# efr32_lcd_hmi.net
KiCad netlist of a schematic drawn in Altium Designer
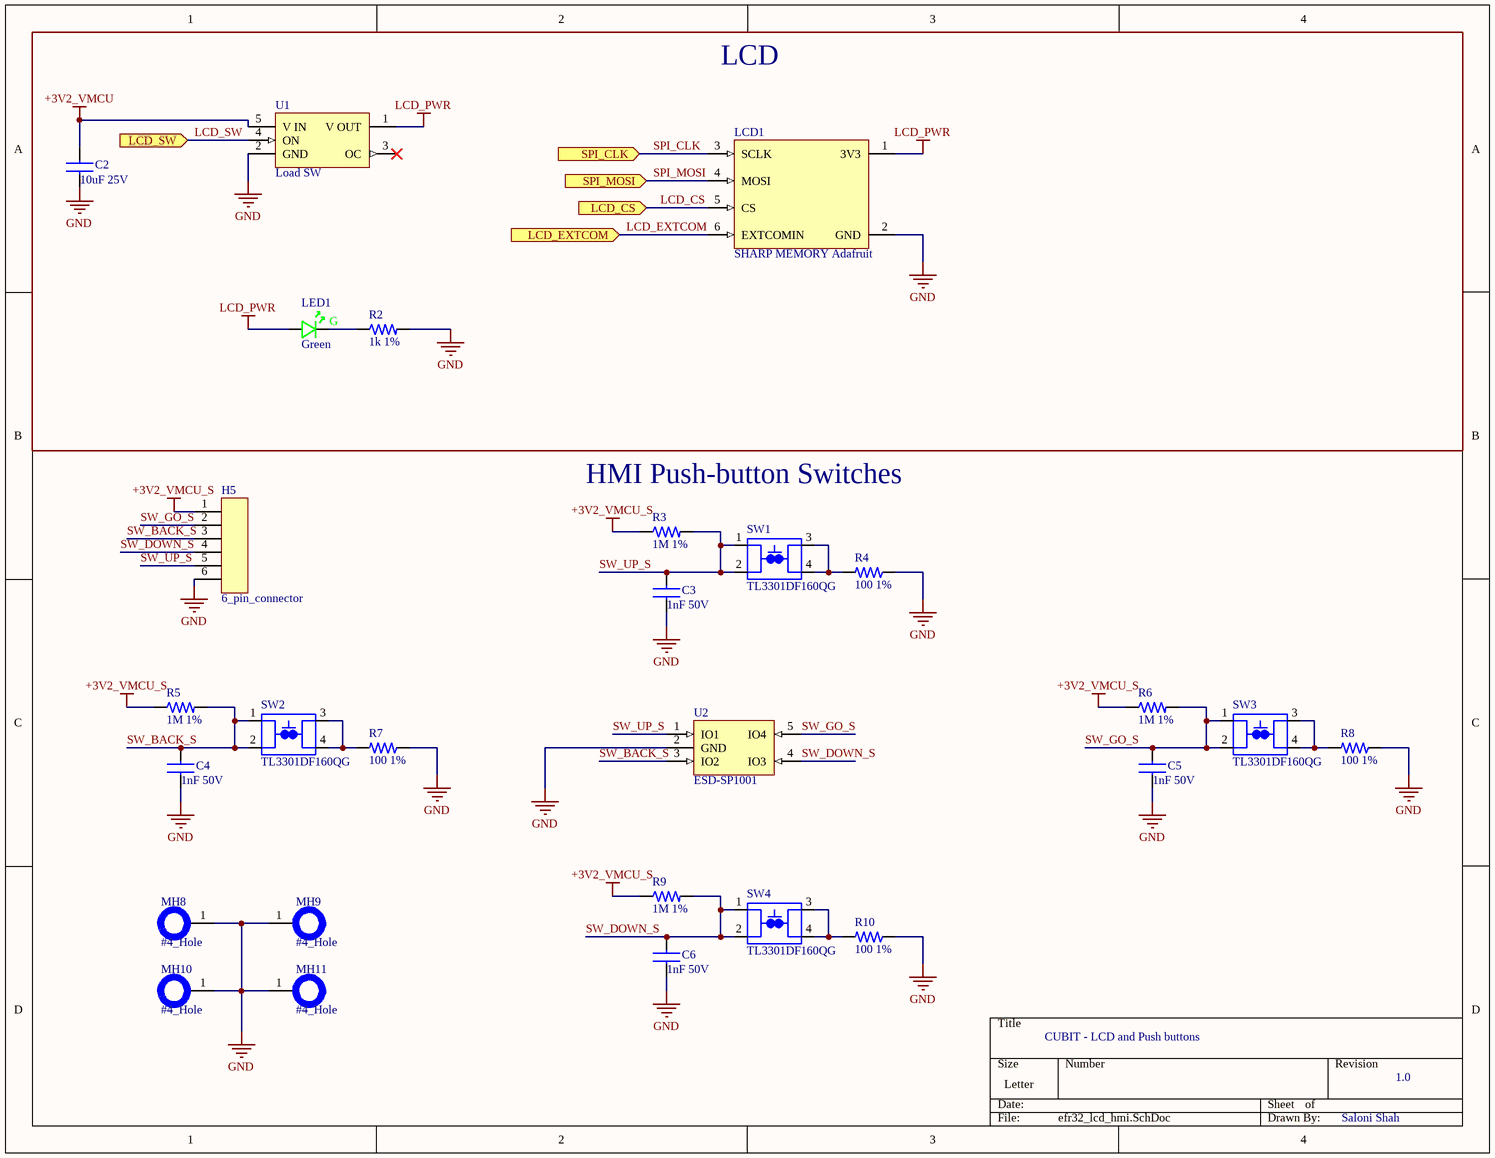
[diagram p0: efr32_lcd_hmi.SchDoc]

(export (version "E")
  (design (tool "Eeschema 10.0.6"))
  (components
    (comp (ref "C2")
      (value "10uF 25V")
      (footprint "LPEDT_proj_lib:CAP_0805_02X125")
      (description "Cap 0805 25 V 10 uF ±20% Tolerance X5R Monolithic Ceramic Chip Capacitor")
      (fields
        (field (name "MANUFACTURER") "Murata")
        (field (name "MANUFACTURER PART NUMBER") "GRM21BR61E106KA73K")
      )
      (libsource (lib "LPEDT_proj_lib") (part "GRM21BR61E106KA73K"))
    )
    (comp (ref "C3")
      (value "1nF 50V")
      (footprint "LPEDT_proj_lib:CAP_0805_02X125")
      (description "1nF ±10% 50V X7R 0805")
      (fields
        (field (name "MANUFACTURER") "Samsung")
        (field (name "MANUFACTURER PART NUMBER") "CL21B102KBANFNC")
      )
      (libsource (lib "LPEDT_proj_lib") (part "CL21B102KBANFNC"))
    )
    (comp (ref "C4")
      (value "1nF 50V")
      (footprint "LPEDT_proj_lib:CAP_0805_02X125")
      (description "1nF ±10% 50V X7R 0805")
      (fields
        (field (name "MANUFACTURER") "Samsung")
        (field (name "MANUFACTURER PART NUMBER") "CL21B102KBANFNC")
      )
      (libsource (lib "LPEDT_proj_lib") (part "CL21B102KBANFNC"))
    )
    (comp (ref "C5")
      (value "1nF 50V")
      (footprint "LPEDT_proj_lib:CAP_0805_02X125")
      (description "1nF ±10% 50V X7R 0805")
      (fields
        (field (name "MANUFACTURER") "Samsung")
        (field (name "MANUFACTURER PART NUMBER") "CL21B102KBANFNC")
      )
      (libsource (lib "LPEDT_proj_lib") (part "CL21B102KBANFNC"))
    )
    (comp (ref "C6")
      (value "1nF 50V")
      (footprint "LPEDT_proj_lib:CAP_0805_02X125")
      (description "1nF ±10% 50V X7R 0805")
      (fields
        (field (name "MANUFACTURER") "Samsung")
        (field (name "MANUFACTURER PART NUMBER") "CL21B102KBANFNC")
      )
      (libsource (lib "LPEDT_proj_lib") (part "CL21B102KBANFNC"))
    )
    (comp (ref "H5")
      (value "6_pin_connector")
      (footprint "6_PIN_100MIL")
      (libsource (lib "LPEDT_proj_lib") (part "6_pin_connector"))
    )
    (comp (ref "LCD1")
      (value "SHARP MEMORY Adafruit")
      (footprint "6_PIN_100MIL")
      (description "Conn AV RCA (Phono) Plug 2 Cont Sz 0.125\" Cbl Mnt Clamp Copper Alloy")
      (fields
        (field (name "MANUFACTURER") "Adafruit Industries")
        (field (name "MANUFACTURER PART NUMBER") "3502")
      )
      (libsource (lib "LPEDT_proj_lib") (part "3502"))
    )
    (comp (ref "LED1")
      (value "Green")
      (footprint "LED_0603_RED_WL-SMCW")
      (description "Led Green Clear 0603 SMD")
      (fields
        (field (name "MANUFACTURER") "QT-Brightek")
        (field (name "MANUFACTURER PART NUMBER") "QBLP601-AG1")
      )
      (libsource (lib "LPEDT_proj_lib") (part "QBLP601-AG1"))
    )
    (comp (ref "MH8")
      (value "#4_Hole")
      (footprint "LPEDT_proj_lib:HOLE_#4")
      (libsource (lib "LPEDT_proj_lib") (part "Mechanical_Hole"))
    )
    (comp (ref "MH9")
      (value "#4_Hole")
      (footprint "LPEDT_proj_lib:HOLE_#4")
      (libsource (lib "LPEDT_proj_lib") (part "Mechanical_Hole"))
    )
    (comp (ref "MH10")
      (value "#4_Hole")
      (footprint "LPEDT_proj_lib:HOLE_#4")
      (libsource (lib "LPEDT_proj_lib") (part "Mechanical_Hole"))
    )
    (comp (ref "MH11")
      (value "#4_Hole")
      (footprint "LPEDT_proj_lib:HOLE_#4")
      (libsource (lib "LPEDT_proj_lib") (part "Mechanical_Hole"))
    )
    (comp (ref "R2")
      (value "1k 1%")
      (footprint "2_Chip_0603_RMCF")
      (description "Res 1K Ohm 1% 0.1W(1/10W) ±100ppm/C Pad SMD Automotive T/R")
      (fields
        (field (name "MANUFACTURER") "Stackpole Electronics")
        (field (name "MANUFACTURER PART NUMBER") "RMCF0603FT1K00")
      )
      (libsource (lib "LPEDT_proj_lib") (part "RMCF0603FT1K00"))
    )
    (comp (ref "R3")
      (value "1M 1%")
      (footprint "2_Chip_0603_RMCF")
      (description "Res 1M Ohm 1% 1/10W ±100ppm/°C Molded SMD Paper T/R")
      (fields
        (field (name "MANUFACTURER") "Stackpole Electronics")
        (field (name "MANUFACTURER PART NUMBER") "RMCF0603FT1M00")
      )
      (libsource (lib "LPEDT_proj_lib") (part "RMCF0603FT1M00"))
    )
    (comp (ref "R4")
      (value "100 1%")
      (footprint "2_Chip_0603_RMCF")
      (description "Res 100 Ohm 1% 1/10W ±100ppm/°C Molded SMD SMD Paper T/R")
      (fields
        (field (name "MANUFACTURER") "Stackpole Electronics")
        (field (name "MANUFACTURER PART NUMBER") "RMCF0603FT100R")
      )
      (libsource (lib "LPEDT_proj_lib") (part "RMCF0603FT100R"))
    )
    (comp (ref "R5")
      (value "1M 1%")
      (footprint "2_Chip_0603_RMCF")
      (description "Res 1M Ohm 1% 1/10W ±100ppm/°C Molded SMD Paper T/R")
      (fields
        (field (name "MANUFACTURER") "Stackpole Electronics")
        (field (name "MANUFACTURER PART NUMBER") "RMCF0603FT1M00")
      )
      (libsource (lib "LPEDT_proj_lib") (part "RMCF0603FT1M00"))
    )
    (comp (ref "R6")
      (value "1M 1%")
      (footprint "2_Chip_0603_RMCF")
      (description "Res 1M Ohm 1% 1/10W ±100ppm/°C Molded SMD Paper T/R")
      (fields
        (field (name "MANUFACTURER") "Stackpole Electronics")
        (field (name "MANUFACTURER PART NUMBER") "RMCF0603FT1M00")
      )
      (libsource (lib "LPEDT_proj_lib") (part "RMCF0603FT1M00"))
    )
    (comp (ref "R7")
      (value "100 1%")
      (footprint "2_Chip_0603_RMCF")
      (description "Res 100 Ohm 1% 1/10W ±100ppm/°C Molded SMD SMD Paper T/R")
      (fields
        (field (name "MANUFACTURER") "Stackpole Electronics")
        (field (name "MANUFACTURER PART NUMBER") "RMCF0603FT100R")
      )
      (libsource (lib "LPEDT_proj_lib") (part "RMCF0603FT100R"))
    )
    (comp (ref "R8")
      (value "100 1%")
      (footprint "2_Chip_0603_RMCF")
      (description "Res 100 Ohm 1% 1/10W ±100ppm/°C Molded SMD SMD Paper T/R")
      (fields
        (field (name "MANUFACTURER") "Stackpole Electronics")
        (field (name "MANUFACTURER PART NUMBER") "RMCF0603FT100R")
      )
      (libsource (lib "LPEDT_proj_lib") (part "RMCF0603FT100R"))
    )
    (comp (ref "R9")
      (value "1M 1%")
      (footprint "2_Chip_0603_RMCF")
      (description "Res 1M Ohm 1% 1/10W ±100ppm/°C Molded SMD Paper T/R")
      (fields
        (field (name "MANUFACTURER") "Stackpole Electronics")
        (field (name "MANUFACTURER PART NUMBER") "RMCF0603FT1M00")
      )
      (libsource (lib "LPEDT_proj_lib") (part "RMCF0603FT1M00"))
    )
    (comp (ref "R10")
      (value "100 1%")
      (footprint "2_Chip_0603_RMCF")
      (description "Res 100 Ohm 1% 1/10W ±100ppm/°C Molded SMD SMD Paper T/R")
      (fields
        (field (name "MANUFACTURER") "Stackpole Electronics")
        (field (name "MANUFACTURER PART NUMBER") "RMCF0603FT100R")
      )
      (libsource (lib "LPEDT_proj_lib") (part "RMCF0603FT100R"))
    )
    (comp (ref "SW1")
      (value "TL3301DF160QG")
      (footprint "SW_TL3301DF160QG")
      (description "Tactile Switch SPST-NO Top Actuated Surface Mount")
      (fields (field (name "MF") "E-Switch"))
      (libsource (lib "LPEDT_proj_lib") (part "TL3301DF160QG"))
    )
    (comp (ref "SW2")
      (value "TL3301DF160QG")
      (footprint "SW_TL3301DF160QG")
      (description "Tactile Switch SPST-NO Top Actuated Surface Mount")
      (fields (field (name "MF") "E-Switch"))
      (libsource (lib "LPEDT_proj_lib") (part "TL3301DF160QG"))
    )
    (comp (ref "SW3")
      (value "TL3301DF160QG")
      (footprint "SW_TL3301DF160QG")
      (description "Tactile Switch SPST-NO Top Actuated Surface Mount")
      (fields (field (name "MF") "E-Switch"))
      (libsource (lib "LPEDT_proj_lib") (part "TL3301DF160QG"))
    )
    (comp (ref "SW4")
      (value "TL3301DF160QG")
      (footprint "SW_TL3301DF160QG")
      (description "Tactile Switch SPST-NO Top Actuated Surface Mount")
      (fields (field (name "MF") "E-Switch"))
      (libsource (lib "LPEDT_proj_lib") (part "TL3301DF160QG"))
    )
    (comp (ref "U1")
      (value "Load SW")
      (footprint "SOT65P210X110-5N")
      (description "5.5-V, 0.1-A, 500-mΩ, load switch with current limit and active low enable 5-SC70 -40 to 85")
      (fields
        (field (name "MANUFACTURER") "Texas Instruments")
        (field (name "MANUFACTURER PART NUMBER") "TPS22942DCKR")
      )
      (libsource (lib "LPEDT_proj_lib") (part "TPS22942DCKR"))
    )
    (comp (ref "U2")
      (value "ESD-SP1001")
      (footprint "SOT65P210X110-5N")
      (description "TVS DIODE 5.5VWM 13VC SC70-5")
      (fields
        (field (name "MANUFACTURER") "Littelfuse")
        (field (name "MANUFACTURER PART NUMBER") "SP1001-04JTG")
      )
      (libsource (lib "LPEDT_proj_lib") (part "SP1001-04JTG"))
    )
  )
  (nets
    (net (code "1") (name "+3V2_VMCU") (class "Default")
      (node (ref "C2") (pin "1") (pinfunction "1_1") (pintype "passive"))
      (node (ref "U1") (pin "5") (pinfunction "V_IN_5") (pintype "power_in"))
    )
    (net (code "2") (name "+3V2_VMCU_S") (class "Default")
      (node (ref "H5") (pin "1") (pintype "power_in"))
      (node (ref "R3") (pin "1") (pinfunction "1_1") (pintype "passive"))
      (node (ref "R5") (pin "1") (pinfunction "1_1") (pintype "passive"))
      (node (ref "R6") (pin "1") (pinfunction "1_1") (pintype "passive"))
      (node (ref "R9") (pin "1") (pinfunction "1_1") (pintype "passive"))
    )
    (net (code "3") (name "/LCD_CS") (class "Default")
      (node (ref "LCD1") (pin "5") (pinfunction "CS_5") (pintype "input"))
    )
    (net (code "4") (name "/LCD_EXTCOM") (class "Default")
      (node (ref "LCD1") (pin "6") (pinfunction "EXTCOMIN_6") (pintype "input"))
    )
    (net (code "5") (name "/LCD_SW") (class "Default")
      (node (ref "U1") (pin "4") (pinfunction "ON_4") (pintype "input"))
    )
    (net (code "6") (name "/SPI_CLK") (class "Default")
      (node (ref "LCD1") (pin "3") (pinfunction "SCLK_3") (pintype "input"))
    )
    (net (code "7") (name "/SPI_MOSI") (class "Default")
      (node (ref "LCD1") (pin "4") (pinfunction "MOSI_4") (pintype "input"))
    )
    (net (code "8") (name "/SW_BACK_S") (class "Default")
      (node (ref "C4") (pin "1") (pinfunction "1_1") (pintype "passive"))
      (node (ref "H5") (pin "3") (pintype "passive"))
      (node (ref "R5") (pin "2") (pinfunction "2_2") (pintype "passive"))
      (node (ref "SW2") (pin "1") (pinfunction "1_1") (pintype "passive"))
      (node (ref "SW2") (pin "2") (pinfunction "2_2") (pintype "passive"))
      (node (ref "U2") (pin "3") (pinfunction "IO2_3") (pintype "input"))
    )
    (net (code "9") (name "/SW_DOWN_S") (class "Default")
      (node (ref "C6") (pin "1") (pinfunction "1_1") (pintype "passive"))
      (node (ref "H5") (pin "4") (pintype "passive"))
      (node (ref "R9") (pin "2") (pinfunction "2_2") (pintype "passive"))
      (node (ref "SW4") (pin "1") (pinfunction "1_1") (pintype "passive"))
      (node (ref "SW4") (pin "2") (pinfunction "2_2") (pintype "passive"))
      (node (ref "U2") (pin "4") (pinfunction "IO3_4") (pintype "input"))
    )
    (net (code "10") (name "/SW_GO_S") (class "Default")
      (node (ref "C5") (pin "1") (pinfunction "1_1") (pintype "passive"))
      (node (ref "H5") (pin "2") (pintype "passive"))
      (node (ref "R6") (pin "2") (pinfunction "2_2") (pintype "passive"))
      (node (ref "SW3") (pin "1") (pinfunction "1_1") (pintype "passive"))
      (node (ref "SW3") (pin "2") (pinfunction "2_2") (pintype "passive"))
      (node (ref "U2") (pin "5") (pinfunction "IO4_5") (pintype "input"))
    )
    (net (code "11") (name "/SW_UP_S") (class "Default")
      (node (ref "C3") (pin "1") (pinfunction "1_1") (pintype "passive"))
      (node (ref "H5") (pin "5") (pintype "passive"))
      (node (ref "R3") (pin "2") (pinfunction "2_2") (pintype "passive"))
      (node (ref "SW1") (pin "1") (pinfunction "1_1") (pintype "passive"))
      (node (ref "SW1") (pin "2") (pinfunction "2_2") (pintype "passive"))
      (node (ref "U2") (pin "1") (pinfunction "IO1_1") (pintype "input"))
    )
    (net (code "12") (name "GND") (class "Default")
      (node (ref "C2") (pin "2") (pinfunction "2_2") (pintype "passive"))
      (node (ref "C3") (pin "2") (pinfunction "2_2") (pintype "passive"))
      (node (ref "C4") (pin "2") (pinfunction "2_2") (pintype "passive"))
      (node (ref "C5") (pin "2") (pinfunction "2_2") (pintype "passive"))
      (node (ref "C6") (pin "2") (pinfunction "2_2") (pintype "passive"))
      (node (ref "H5") (pin "6") (pintype "power_in"))
      (node (ref "LCD1") (pin "2") (pinfunction "GND_2") (pintype "power_in"))
      (node (ref "MH10") (pin "1") (pinfunction "1_1") (pintype "passive"))
      (node (ref "MH11") (pin "1") (pinfunction "1_1") (pintype "passive"))
      (node (ref "MH8") (pin "1") (pinfunction "1_1") (pintype "passive"))
      (node (ref "MH9") (pin "1") (pinfunction "1_1") (pintype "passive"))
      (node (ref "R10") (pin "1") (pinfunction "1_1") (pintype "passive"))
      (node (ref "R2") (pin "2") (pinfunction "2_2") (pintype "passive"))
      (node (ref "R4") (pin "1") (pinfunction "1_1") (pintype "passive"))
      (node (ref "R7") (pin "1") (pinfunction "1_1") (pintype "passive"))
      (node (ref "R8") (pin "1") (pinfunction "1_1") (pintype "passive"))
      (node (ref "U1") (pin "2") (pinfunction "GND_2") (pintype "power_in"))
      (node (ref "U2") (pin "2") (pinfunction "GND_2") (pintype "power_in"))
    )
    (net (code "13") (name "LCD_PWR") (class "Default")
      (node (ref "LCD1") (pin "1") (pinfunction "3V3_1") (pintype "power_in"))
      (node (ref "LED1") (pin "A") (pinfunction "A_A") (pintype "passive"))
      (node (ref "U1") (pin "1") (pinfunction "V_OUT_1") (pintype "power_in"))
    )
    (net (code "14") (name "Net-(LED1-PadC)") (class "Default")
      (node (ref "LED1") (pin "C") (pinfunction "C_C") (pintype "passive"))
      (node (ref "R2") (pin "1") (pinfunction "1_1") (pintype "passive"))
    )
    (net (code "15") (name "Net-(R4-Pad2)") (class "Default")
      (node (ref "R4") (pin "2") (pinfunction "2_2") (pintype "passive"))
      (node (ref "SW1") (pin "3") (pinfunction "3_3") (pintype "passive"))
      (node (ref "SW1") (pin "4") (pinfunction "4_4") (pintype "passive"))
    )
    (net (code "16") (name "Net-(R7-Pad2)") (class "Default")
      (node (ref "R7") (pin "2") (pinfunction "2_2") (pintype "passive"))
      (node (ref "SW2") (pin "3") (pinfunction "3_3") (pintype "passive"))
      (node (ref "SW2") (pin "4") (pinfunction "4_4") (pintype "passive"))
    )
    (net (code "17") (name "Net-(R8-Pad2)") (class "Default")
      (node (ref "R8") (pin "2") (pinfunction "2_2") (pintype "passive"))
      (node (ref "SW3") (pin "3") (pinfunction "3_3") (pintype "passive"))
      (node (ref "SW3") (pin "4") (pinfunction "4_4") (pintype "passive"))
    )
    (net (code "18") (name "Net-(R10-Pad2)") (class "Default")
      (node (ref "R10") (pin "2") (pinfunction "2_2") (pintype "passive"))
      (node (ref "SW4") (pin "3") (pinfunction "3_3") (pintype "passive"))
      (node (ref "SW4") (pin "4") (pinfunction "4_4") (pintype "passive"))
    )
    (net (code "19") (name "unconnected-(U1-OC-Pad3)") (class "Default")
      (node (ref "U1") (pin "3") (pinfunction "OC_3") (pintype "output+no_connect"))
    )
  )
)
